# BUS_LCD.net
KiCad netlist of a schematic drawn in Altium Designer
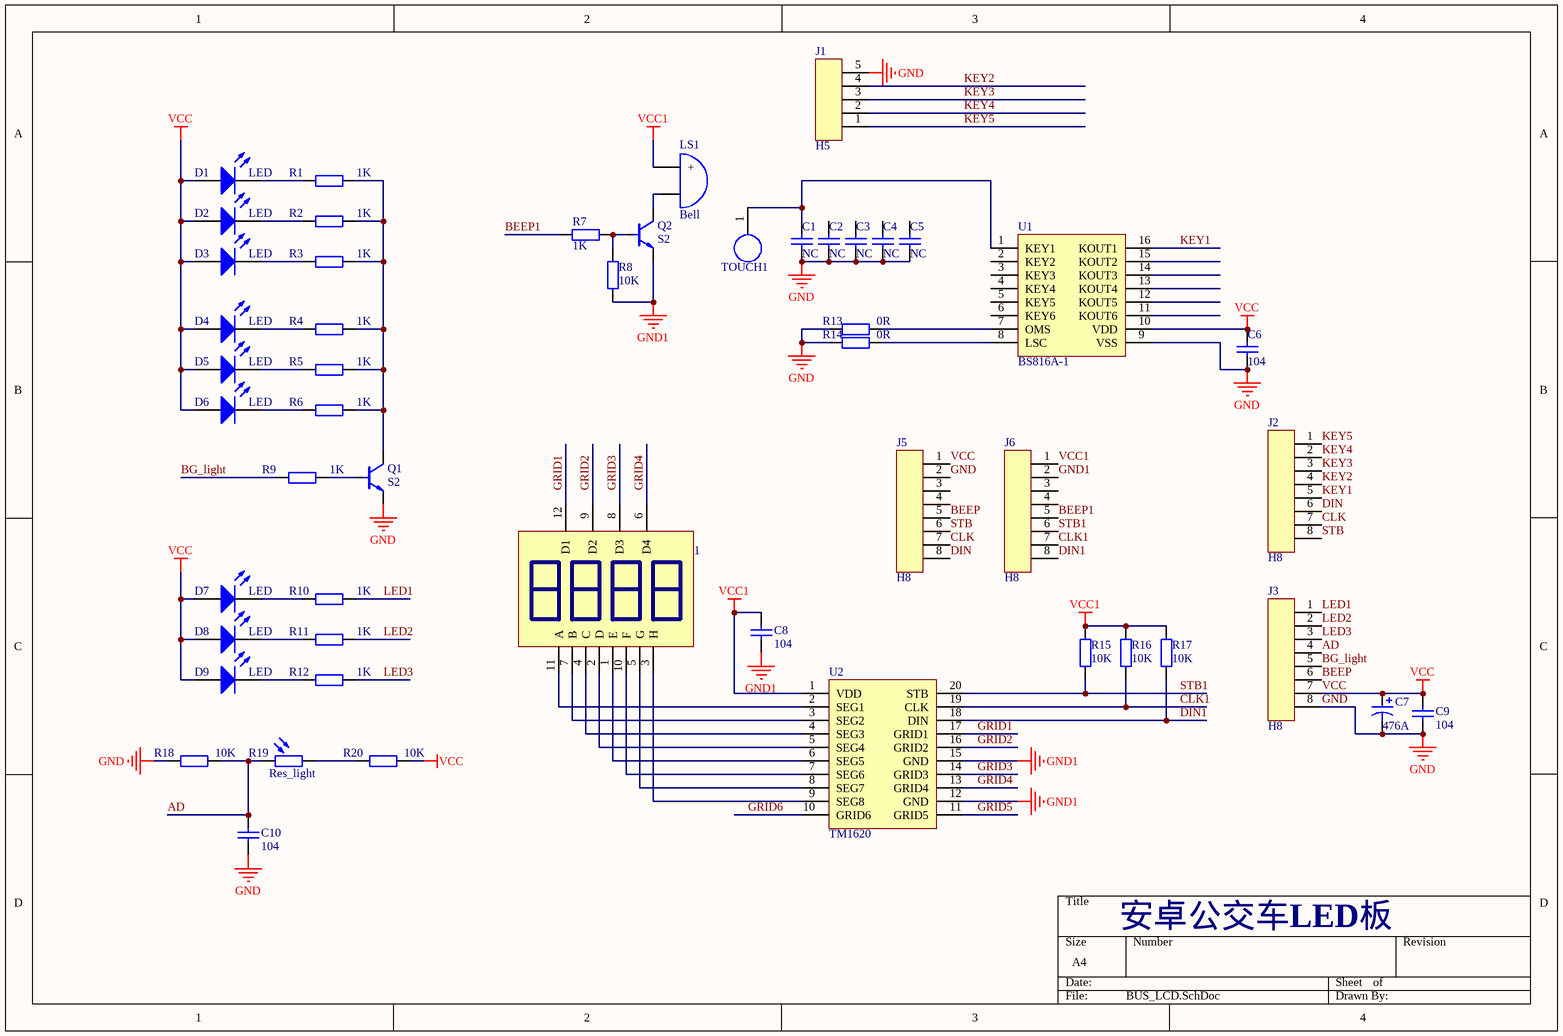
[diagram p0: BUS_LCD.SchDoc]

(export (version "E")
  (design (tool "Eeschema 10.0.6"))
  (components
    (comp (ref "1")
      (value "7SEG-MPX4")
      (footprint "7SEG-MPX4-0.36")
      (libsource (lib "QB-Special-Schlib") (part "7SEG-MPX4"))
    )
    (comp (ref "C1")
      (value "NC")
      (footprint "C0603")
      (description "Capacitor")
      (fields (field (name "PUBLISHER") "Altium Limited"))
      (libsource (lib "QB-General-Schlib") (part "Cap"))
    )
    (comp (ref "C2")
      (value "NC")
      (footprint "C0603")
      (description "Capacitor")
      (fields (field (name "PUBLISHER") "Altium Limited"))
      (libsource (lib "QB-General-Schlib") (part "Cap"))
    )
    (comp (ref "C3")
      (value "NC")
      (footprint "C0603")
      (description "Capacitor")
      (fields (field (name "PUBLISHER") "Altium Limited"))
      (libsource (lib "QB-General-Schlib") (part "Cap"))
    )
    (comp (ref "C4")
      (value "NC")
      (footprint "C0603")
      (description "Capacitor")
      (fields (field (name "PUBLISHER") "Altium Limited"))
      (libsource (lib "QB-General-Schlib") (part "Cap"))
    )
    (comp (ref "C5")
      (value "NC")
      (footprint "C0603")
      (description "Capacitor")
      (fields (field (name "PUBLISHER") "Altium Limited"))
      (libsource (lib "QB-General-Schlib") (part "Cap"))
    )
    (comp (ref "C6")
      (value "104")
      (footprint "C0603")
      (description "Capacitor")
      (fields (field (name "PUBLISHER") "Altium Limited"))
      (libsource (lib "QB-General-Schlib") (part "Cap"))
    )
    (comp (ref "C7")
      (value "476A")
      (footprint "476A")
      (description "Polarized Capacitor")
      (fields (field (name "PUBLISHER") "Altium Limited"))
      (libsource (lib "QB-General-Schlib") (part "Cap Pol"))
    )
    (comp (ref "C8")
      (value "104")
      (footprint "C0603")
      (description "Capacitor")
      (fields (field (name "PUBLISHER") "Altium Limited"))
      (libsource (lib "QB-General-Schlib") (part "Cap"))
    )
    (comp (ref "C9")
      (value "104")
      (footprint "C0603")
      (description "Capacitor")
      (fields (field (name "PUBLISHER") "Altium Limited"))
      (libsource (lib "QB-General-Schlib") (part "Cap"))
    )
    (comp (ref "C10")
      (value "104")
      (footprint "C0603")
      (description "Capacitor")
      (fields (field (name "PUBLISHER") "Altium Limited"))
      (libsource (lib "QB-General-Schlib") (part "Cap"))
    )
    (comp (ref "D1")
      (value "LED")
      (footprint "LED0805-SMT")
      (description "LED light")
      (libsource (lib "QB-General-Schlib") (part "LED"))
    )
    (comp (ref "D2")
      (value "LED")
      (footprint "LED0805-SMT")
      (description "LED light")
      (libsource (lib "QB-General-Schlib") (part "LED"))
    )
    (comp (ref "D3")
      (value "LED")
      (footprint "LED0805-SMT")
      (description "LED light")
      (libsource (lib "QB-General-Schlib") (part "LED"))
    )
    (comp (ref "D4")
      (value "LED")
      (footprint "LED0805-SMT")
      (description "LED light")
      (libsource (lib "QB-General-Schlib") (part "LED"))
    )
    (comp (ref "D5")
      (value "LED")
      (footprint "LED0805-SMT")
      (description "LED light")
      (libsource (lib "QB-General-Schlib") (part "LED"))
    )
    (comp (ref "D6")
      (value "LED")
      (footprint "LED0805-SMT")
      (description "LED light")
      (libsource (lib "QB-General-Schlib") (part "LED"))
    )
    (comp (ref "D7")
      (value "LED")
      (footprint "LED0805-SMT")
      (description "LED light")
      (libsource (lib "QB-General-Schlib") (part "LED"))
    )
    (comp (ref "D8")
      (value "LED")
      (footprint "LED0805-SMT")
      (description "LED light")
      (libsource (lib "QB-General-Schlib") (part "LED"))
    )
    (comp (ref "D9")
      (value "LED")
      (footprint "LED0805-SMT")
      (description "LED light")
      (libsource (lib "QB-General-Schlib") (part "LED"))
    )
    (comp (ref "J1") (value "H5") (footprint "H5_2.54") (libsource (lib "QB-Connector-Schlib") (part "H5")))
    (comp (ref "J2")
      (value "H8")
      (footprint "1.25-8P-LT")
      (libsource (lib "QB-Connector-Schlib") (part "H8"))
    )
    (comp (ref "J3")
      (value "H8")
      (footprint "1.25-8P-LT")
      (libsource (lib "QB-Connector-Schlib") (part "H8"))
    )
    (comp (ref "J5")
      (value "H8")
      (footprint "1.25-8P-LT")
      (libsource (lib "QB-Connector-Schlib") (part "H8"))
    )
    (comp (ref "J6")
      (value "H8")
      (footprint "1.25-8P-LT")
      (libsource (lib "QB-Connector-Schlib") (part "H8"))
    )
    (comp (ref "LS1")
      (value "Bell")
      (footprint "Bell_12*9")
      (description "Electrical Bell")
      (fields (field (name "PUBLISHER") "Altium Limited"))
      (libsource (lib "QB-Special-Schlib") (part "Bell"))
    )
    (comp (ref "Q1")
      (value "S2")
      (footprint "SOT-23")
      (description "NPN General Purpose Amplifier")
      (libsource (lib "QB-General-Schlib") (part "NPN"))
    )
    (comp (ref "Q2")
      (value "S2")
      (footprint "SOT-23")
      (description "NPN General Purpose Amplifier")
      (libsource (lib "QB-General-Schlib") (part "NPN"))
    )
    (comp (ref "R1")
      (value "1K")
      (footprint "R0603")
      (description "Resistor")
      (fields (field (name "PUBLISHER") "Altium Limited"))
      (libsource (lib "QB-General-Schlib") (part "Res"))
    )
    (comp (ref "R2")
      (value "1K")
      (footprint "R0603")
      (description "Resistor")
      (fields (field (name "PUBLISHER") "Altium Limited"))
      (libsource (lib "QB-General-Schlib") (part "Res"))
    )
    (comp (ref "R3")
      (value "1K")
      (footprint "R0603")
      (description "Resistor")
      (fields (field (name "PUBLISHER") "Altium Limited"))
      (libsource (lib "QB-General-Schlib") (part "Res"))
    )
    (comp (ref "R4")
      (value "1K")
      (footprint "R0603")
      (description "Resistor")
      (fields (field (name "PUBLISHER") "Altium Limited"))
      (libsource (lib "QB-General-Schlib") (part "Res"))
    )
    (comp (ref "R5")
      (value "1K")
      (footprint "R0603")
      (description "Resistor")
      (fields (field (name "PUBLISHER") "Altium Limited"))
      (libsource (lib "QB-General-Schlib") (part "Res"))
    )
    (comp (ref "R6")
      (value "1K")
      (footprint "R0603")
      (description "Resistor")
      (fields (field (name "PUBLISHER") "Altium Limited"))
      (libsource (lib "QB-General-Schlib") (part "Res"))
    )
    (comp (ref "R7")
      (value "1K")
      (footprint "0603R")
      (description "Resistor")
      (fields (field (name "PUBLISHER") "Altium Limited"))
      (libsource (lib "QB-General-Schlib") (part "Res"))
    )
    (comp (ref "R8")
      (value "10K")
      (footprint "0603R")
      (description "Resistor")
      (fields (field (name "PUBLISHER") "Altium Limited"))
      (libsource (lib "") (part "Res_2"))
    )
    (comp (ref "R9")
      (value "1K")
      (footprint "R0603")
      (description "Resistor")
      (fields (field (name "PUBLISHER") "Altium Limited"))
      (libsource (lib "QB-General-Schlib") (part "Res"))
    )
    (comp (ref "R10")
      (value "1K")
      (footprint "R0603")
      (description "Resistor")
      (fields (field (name "PUBLISHER") "Altium Limited"))
      (libsource (lib "QB-General-Schlib") (part "Res"))
    )
    (comp (ref "R11")
      (value "1K")
      (footprint "R0603")
      (description "Resistor")
      (fields (field (name "PUBLISHER") "Altium Limited"))
      (libsource (lib "QB-General-Schlib") (part "Res"))
    )
    (comp (ref "R12")
      (value "1K")
      (footprint "R0603")
      (description "Resistor")
      (fields (field (name "PUBLISHER") "Altium Limited"))
      (libsource (lib "QB-General-Schlib") (part "Res"))
    )
    (comp (ref "R13")
      (value "0R")
      (footprint "R0603")
      (description "Resistor")
      (fields (field (name "PUBLISHER") "Altium Limited"))
      (libsource (lib "") (part "Res_1"))
    )
    (comp (ref "R14")
      (value "0R")
      (footprint "R0603")
      (description "Resistor")
      (fields (field (name "PUBLISHER") "Altium Limited"))
      (libsource (lib "") (part "Res_1"))
    )
    (comp (ref "R15")
      (value "10K")
      (footprint "R0603")
      (description "Resistor")
      (fields (field (name "PUBLISHER") "Altium Limited"))
      (libsource (lib "") (part "Res_2"))
    )
    (comp (ref "R16")
      (value "10K")
      (footprint "R0603")
      (description "Resistor")
      (fields (field (name "PUBLISHER") "Altium Limited"))
      (libsource (lib "") (part "Res_2"))
    )
    (comp (ref "R17")
      (value "10K")
      (footprint "R0603")
      (description "Resistor")
      (fields (field (name "PUBLISHER") "Altium Limited"))
      (libsource (lib "") (part "Res_2"))
    )
    (comp (ref "R18")
      (value "10K")
      (footprint "R0603")
      (description "Resistor")
      (fields (field (name "PUBLISHER") "Altium Limited"))
      (libsource (lib "QB-General-Schlib") (part "Res"))
    )
    (comp (ref "R19")
      (value "Res_light")
      (footprint "LED0805-SMT")
      (description "Light Dependent Rsistors")
      (fields (field (name "PUBLISHER") "Altium Limited"))
      (libsource (lib "QB-General-Schlib") (part "Res_light"))
    )
    (comp (ref "R20")
      (value "10K")
      (footprint "R0603")
      (description "Resistor")
      (fields (field (name "PUBLISHER") "Altium Limited"))
      (libsource (lib "QB-General-Schlib") (part "Res"))
    )
    (comp (ref "TOUCH1")
      (value "TouchKey1")
      (footprint "TOUCHKEY6")
      (libsource (lib "QB-Special-Schlib") (part "TouchKey1"))
    )
    (comp (ref "U1")
      (value "BS816A-1")
      (footprint "SO-16")
      (libsource (lib "QB-Chip-Schlib") (part "BS816A-1"))
    )
    (comp (ref "U2")
      (value "TM1620")
      (footprint "SOJ-20")
      (description "数码管驱动")
      (libsource (lib "QB-Chip-Schlib") (part "TM1620"))
    )
  )
  (nets
    (net (code "1") (name "/AD") (class "Default")
      (node (ref "C10") (pin "2") (pinfunction "2_2") (pintype "passive"))
      (node (ref "J3") (pin "4") (pinfunction "4_4") (pintype "passive"))
      (node (ref "R18") (pin "2") (pinfunction "2_2") (pintype "passive"))
      (node (ref "R19") (pin "2") (pinfunction "2_2") (pintype "passive"))
    )
    (net (code "2") (name "/BEEP") (class "Default")
      (node (ref "J3") (pin "6") (pinfunction "6_6") (pintype "passive"))
      (node (ref "J5") (pin "5") (pinfunction "5_5") (pintype "passive"))
    )
    (net (code "3") (name "/BEEP1") (class "Default")
      (node (ref "J6") (pin "5") (pinfunction "5_5") (pintype "passive"))
      (node (ref "R7") (pin "1") (pinfunction "1_1") (pintype "passive"))
    )
    (net (code "4") (name "/BG_light") (class "Default")
      (node (ref "J3") (pin "5") (pinfunction "5_5") (pintype "passive"))
      (node (ref "R9") (pin "1") (pinfunction "1_1") (pintype "passive"))
    )
    (net (code "5") (name "/CLK") (class "Default")
      (node (ref "J2") (pin "7") (pinfunction "7_7") (pintype "passive"))
      (node (ref "J5") (pin "7") (pinfunction "7_7") (pintype "passive"))
    )
    (net (code "6") (name "/CLK1") (class "Default")
      (node (ref "J6") (pin "7") (pinfunction "7_7") (pintype "passive"))
      (node (ref "R16") (pin "1") (pinfunction "1_1") (pintype "passive"))
      (node (ref "U2") (pin "19") (pinfunction "CLK_19") (pintype "passive"))
    )
    (net (code "7") (name "/DIN") (class "Default")
      (node (ref "J2") (pin "6") (pinfunction "6_6") (pintype "passive"))
      (node (ref "J5") (pin "8") (pinfunction "8_8") (pintype "passive"))
    )
    (net (code "8") (name "/DIN1") (class "Default")
      (node (ref "J6") (pin "8") (pinfunction "8_8") (pintype "passive"))
      (node (ref "R17") (pin "1") (pinfunction "1_1") (pintype "passive"))
      (node (ref "U2") (pin "18") (pinfunction "DIN_18") (pintype "passive"))
    )
    (net (code "9") (name "/GRID1") (class "Default")
      (node (ref "1") (pin "12") (pinfunction "D1_12") (pintype "passive"))
      (node (ref "U2") (pin "17") (pinfunction "GRID1_17") (pintype "passive"))
    )
    (net (code "10") (name "/GRID2") (class "Default")
      (node (ref "1") (pin "9") (pinfunction "D2_9") (pintype "passive"))
      (node (ref "U2") (pin "16") (pinfunction "GRID2_16") (pintype "passive"))
    )
    (net (code "11") (name "/GRID3") (class "Default")
      (node (ref "1") (pin "8") (pinfunction "D3_8") (pintype "passive"))
      (node (ref "U2") (pin "14") (pinfunction "GRID3_14") (pintype "passive"))
    )
    (net (code "12") (name "/GRID4") (class "Default")
      (node (ref "1") (pin "6") (pinfunction "D4_6") (pintype "passive"))
      (node (ref "U2") (pin "13") (pinfunction "GRID4_13") (pintype "passive"))
    )
    (net (code "13") (name "/GRID5") (class "Default")
      (node (ref "U2") (pin "11") (pinfunction "GRID5_11") (pintype "passive"))
    )
    (net (code "14") (name "/GRID6") (class "Default")
      (node (ref "U2") (pin "10") (pinfunction "GRID6_10") (pintype "passive"))
    )
    (net (code "15") (name "/KEY1") (class "Default")
      (node (ref "J2") (pin "5") (pinfunction "5_5") (pintype "passive"))
      (node (ref "U1") (pin "16") (pinfunction "KOUT1_16") (pintype "passive"))
    )
    (net (code "16") (name "/KEY2") (class "Default")
      (node (ref "J1") (pin "4") (pinfunction "4_4") (pintype "passive"))
      (node (ref "J2") (pin "4") (pinfunction "4_4") (pintype "passive"))
    )
    (net (code "17") (name "/KEY3") (class "Default")
      (node (ref "J1") (pin "3") (pinfunction "3_3") (pintype "passive"))
      (node (ref "J2") (pin "3") (pinfunction "3_3") (pintype "passive"))
    )
    (net (code "18") (name "/KEY4") (class "Default")
      (node (ref "J1") (pin "2") (pinfunction "2_2") (pintype "passive"))
      (node (ref "J2") (pin "2") (pinfunction "2_2") (pintype "passive"))
    )
    (net (code "19") (name "/KEY5") (class "Default")
      (node (ref "J1") (pin "1") (pinfunction "1_1") (pintype "passive"))
      (node (ref "J2") (pin "1") (pinfunction "1_1") (pintype "passive"))
    )
    (net (code "20") (name "/LED1") (class "Default")
      (node (ref "J3") (pin "1") (pinfunction "1_1") (pintype "passive"))
      (node (ref "R10") (pin "2") (pinfunction "2_2") (pintype "passive"))
    )
    (net (code "21") (name "/LED2") (class "Default")
      (node (ref "J3") (pin "2") (pinfunction "2_2") (pintype "passive"))
      (node (ref "R11") (pin "2") (pinfunction "2_2") (pintype "passive"))
    )
    (net (code "22") (name "/LED3") (class "Default")
      (node (ref "J3") (pin "3") (pinfunction "3_3") (pintype "passive"))
      (node (ref "R12") (pin "2") (pinfunction "2_2") (pintype "passive"))
    )
    (net (code "23") (name "/STB") (class "Default")
      (node (ref "J2") (pin "8") (pinfunction "8_8") (pintype "passive"))
      (node (ref "J5") (pin "6") (pinfunction "6_6") (pintype "passive"))
    )
    (net (code "24") (name "/STB1") (class "Default")
      (node (ref "J6") (pin "6") (pinfunction "6_6") (pintype "passive"))
      (node (ref "R15") (pin "1") (pinfunction "1_1") (pintype "passive"))
      (node (ref "U2") (pin "20") (pinfunction "STB_20") (pintype "passive"))
    )
    (net (code "25") (name "GND") (class "Default")
      (node (ref "C1") (pin "1") (pinfunction "1_1") (pintype "passive"))
      (node (ref "C10") (pin "1") (pinfunction "1_1") (pintype "passive"))
      (node (ref "C2") (pin "1") (pinfunction "1_1") (pintype "passive"))
      (node (ref "C3") (pin "1") (pinfunction "1_1") (pintype "passive"))
      (node (ref "C4") (pin "1") (pinfunction "1_1") (pintype "passive"))
      (node (ref "C5") (pin "1") (pinfunction "1_1") (pintype "passive"))
      (node (ref "C6") (pin "1") (pinfunction "1_1") (pintype "passive"))
      (node (ref "C7") (pin "2") (pinfunction "2_2") (pintype "passive"))
      (node (ref "C9") (pin "1") (pinfunction "1_1") (pintype "passive"))
      (node (ref "J1") (pin "5") (pinfunction "5_5") (pintype "passive"))
      (node (ref "J3") (pin "8") (pinfunction "8_8") (pintype "passive"))
      (node (ref "J5") (pin "2") (pinfunction "2_2") (pintype "passive"))
      (node (ref "Q1") (pin "1") (pinfunction "e_1") (pintype "passive"))
      (node (ref "R13") (pin "2") (pinfunction "2_2") (pintype "passive"))
      (node (ref "R14") (pin "2") (pinfunction "2_2") (pintype "passive"))
      (node (ref "R18") (pin "1") (pinfunction "1_1") (pintype "passive"))
      (node (ref "U1") (pin "9") (pinfunction "VSS_9") (pintype "passive"))
    )
    (net (code "26") (name "GND1") (class "Default")
      (node (ref "C8") (pin "1") (pinfunction "1_1") (pintype "passive"))
      (node (ref "J6") (pin "2") (pinfunction "2_2") (pintype "passive"))
      (node (ref "Q2") (pin "1") (pinfunction "e_1") (pintype "passive"))
      (node (ref "R8") (pin "1") (pinfunction "1_1") (pintype "passive"))
      (node (ref "U2") (pin "12") (pinfunction "GND_12") (pintype "passive"))
      (node (ref "U2") (pin "15") (pinfunction "GND_15") (pintype "passive"))
    )
    (net (code "27") (name "Net-(1-A)") (class "Default")
      (node (ref "1") (pin "11") (pinfunction "A_11") (pintype "passive"))
      (node (ref "U2") (pin "2") (pinfunction "SEG1_2") (pintype "passive"))
    )
    (net (code "28") (name "Net-(1-B)") (class "Default")
      (node (ref "1") (pin "7") (pinfunction "B_7") (pintype "passive"))
      (node (ref "U2") (pin "3") (pinfunction "SEG2_3") (pintype "passive"))
    )
    (net (code "29") (name "Net-(1-C)") (class "Default")
      (node (ref "1") (pin "4") (pinfunction "C_4") (pintype "passive"))
      (node (ref "U2") (pin "4") (pinfunction "SEG3_4") (pintype "passive"))
    )
    (net (code "30") (name "Net-(1-D)") (class "Default")
      (node (ref "1") (pin "2") (pinfunction "D_2") (pintype "passive"))
      (node (ref "U2") (pin "5") (pinfunction "SEG4_5") (pintype "passive"))
    )
    (net (code "31") (name "Net-(1-E)") (class "Default")
      (node (ref "1") (pin "1") (pinfunction "E_1") (pintype "passive"))
      (node (ref "U2") (pin "6") (pinfunction "SEG5_6") (pintype "passive"))
    )
    (net (code "32") (name "Net-(1-F)") (class "Default")
      (node (ref "1") (pin "10") (pinfunction "F_10") (pintype "passive"))
      (node (ref "U2") (pin "7") (pinfunction "SEG6_7") (pintype "passive"))
    )
    (net (code "33") (name "Net-(1-G)") (class "Default")
      (node (ref "1") (pin "5") (pinfunction "G_5") (pintype "passive"))
      (node (ref "U2") (pin "8") (pinfunction "SEG7_8") (pintype "passive"))
    )
    (net (code "34") (name "Net-(1-H)") (class "Default")
      (node (ref "1") (pin "3") (pinfunction "H_3") (pintype "passive"))
      (node (ref "U2") (pin "9") (pinfunction "SEG8_9") (pintype "passive"))
    )
    (net (code "35") (name "Net-(D1-K)") (class "Default")
      (node (ref "D1") (pin "2") (pinfunction "K_2") (pintype "passive"))
      (node (ref "R1") (pin "1") (pinfunction "1_1") (pintype "passive"))
    )
    (net (code "36") (name "Net-(D2-K)") (class "Default")
      (node (ref "D2") (pin "2") (pinfunction "K_2") (pintype "passive"))
      (node (ref "R2") (pin "1") (pinfunction "1_1") (pintype "passive"))
    )
    (net (code "37") (name "Net-(D3-K)") (class "Default")
      (node (ref "D3") (pin "2") (pinfunction "K_2") (pintype "passive"))
      (node (ref "R3") (pin "1") (pinfunction "1_1") (pintype "passive"))
    )
    (net (code "38") (name "Net-(D4-K)") (class "Default")
      (node (ref "D4") (pin "2") (pinfunction "K_2") (pintype "passive"))
      (node (ref "R4") (pin "1") (pinfunction "1_1") (pintype "passive"))
    )
    (net (code "39") (name "Net-(D5-K)") (class "Default")
      (node (ref "D5") (pin "2") (pinfunction "K_2") (pintype "passive"))
      (node (ref "R5") (pin "1") (pinfunction "1_1") (pintype "passive"))
    )
    (net (code "40") (name "Net-(D6-K)") (class "Default")
      (node (ref "D6") (pin "2") (pinfunction "K_2") (pintype "passive"))
      (node (ref "R6") (pin "1") (pinfunction "1_1") (pintype "passive"))
    )
    (net (code "41") (name "Net-(D7-K)") (class "Default")
      (node (ref "D7") (pin "2") (pinfunction "K_2") (pintype "passive"))
      (node (ref "R10") (pin "1") (pinfunction "1_1") (pintype "passive"))
    )
    (net (code "42") (name "Net-(D8-K)") (class "Default")
      (node (ref "D8") (pin "2") (pinfunction "K_2") (pintype "passive"))
      (node (ref "R11") (pin "1") (pinfunction "1_1") (pintype "passive"))
    )
    (net (code "43") (name "Net-(D9-K)") (class "Default")
      (node (ref "D9") (pin "2") (pinfunction "K_2") (pintype "passive"))
      (node (ref "R12") (pin "1") (pinfunction "1_1") (pintype "passive"))
    )
    (net (code "44") (name "Net-(LS1--)") (class "Default")
      (node (ref "LS1") (pin "2") (pinfunction "-_2") (pintype "passive"))
      (node (ref "Q2") (pin "3") (pinfunction "c_3") (pintype "passive"))
    )
    (net (code "45") (name "Net-(Q1-b)") (class "Default")
      (node (ref "Q1") (pin "2") (pinfunction "b_2") (pintype "passive"))
      (node (ref "R9") (pin "2") (pinfunction "2_2") (pintype "passive"))
    )
    (net (code "46") (name "Net-(Q1-c)") (class "Default")
      (node (ref "Q1") (pin "3") (pinfunction "c_3") (pintype "passive"))
      (node (ref "R1") (pin "2") (pinfunction "2_2") (pintype "passive"))
      (node (ref "R2") (pin "2") (pinfunction "2_2") (pintype "passive"))
      (node (ref "R3") (pin "2") (pinfunction "2_2") (pintype "passive"))
      (node (ref "R4") (pin "2") (pinfunction "2_2") (pintype "passive"))
      (node (ref "R5") (pin "2") (pinfunction "2_2") (pintype "passive"))
      (node (ref "R6") (pin "2") (pinfunction "2_2") (pintype "passive"))
    )
    (net (code "47") (name "Net-(Q2-b)") (class "Default")
      (node (ref "Q2") (pin "2") (pinfunction "b_2") (pintype "passive"))
      (node (ref "R7") (pin "2") (pinfunction "2_2") (pintype "passive"))
      (node (ref "R8") (pin "2") (pinfunction "2_2") (pintype "passive"))
    )
    (net (code "48") (name "Net-(R19-Pad1)") (class "Default")
      (node (ref "R19") (pin "1") (pinfunction "1_1") (pintype "passive"))
      (node (ref "R20") (pin "1") (pinfunction "1_1") (pintype "passive"))
    )
    (net (code "49") (name "Net-(U1-KEY1)") (class "Default")
      (node (ref "C1") (pin "2") (pinfunction "2_2") (pintype "passive"))
      (node (ref "TOUCH1") (pin "1") (pinfunction "1_1") (pintype "passive"))
      (node (ref "U1") (pin "1") (pinfunction "KEY1_1") (pintype "passive"))
    )
    (net (code "50") (name "Net-(U1-LSC)") (class "Default")
      (node (ref "R14") (pin "1") (pinfunction "1_1") (pintype "passive"))
      (node (ref "U1") (pin "8") (pinfunction "LSC_8") (pintype "passive"))
    )
    (net (code "51") (name "Net-(U1-OMS)") (class "Default")
      (node (ref "R13") (pin "1") (pinfunction "1_1") (pintype "passive"))
      (node (ref "U1") (pin "7") (pinfunction "OMS_7") (pintype "passive"))
    )
    (net (code "52") (name "VCC") (class "Default")
      (node (ref "C6") (pin "2") (pinfunction "2_2") (pintype "passive"))
      (node (ref "C7") (pin "1") (pinfunction "1_1") (pintype "passive"))
      (node (ref "C9") (pin "2") (pinfunction "2_2") (pintype "passive"))
      (node (ref "D1") (pin "1") (pinfunction "A_1") (pintype "passive"))
      (node (ref "D2") (pin "1") (pinfunction "A_1") (pintype "passive"))
      (node (ref "D3") (pin "1") (pinfunction "A_1") (pintype "passive"))
      (node (ref "D4") (pin "1") (pinfunction "A_1") (pintype "passive"))
      (node (ref "D5") (pin "1") (pinfunction "A_1") (pintype "passive"))
      (node (ref "D6") (pin "1") (pinfunction "A_1") (pintype "passive"))
      (node (ref "D7") (pin "1") (pinfunction "A_1") (pintype "passive"))
      (node (ref "D8") (pin "1") (pinfunction "A_1") (pintype "passive"))
      (node (ref "D9") (pin "1") (pinfunction "A_1") (pintype "passive"))
      (node (ref "J3") (pin "7") (pinfunction "7_7") (pintype "passive"))
      (node (ref "J5") (pin "1") (pinfunction "1_1") (pintype "passive"))
      (node (ref "R20") (pin "2") (pinfunction "2_2") (pintype "passive"))
      (node (ref "U1") (pin "10") (pinfunction "VDD_10") (pintype "passive"))
    )
    (net (code "53") (name "VCC1") (class "Default")
      (node (ref "C8") (pin "2") (pinfunction "2_2") (pintype "passive"))
      (node (ref "J6") (pin "1") (pinfunction "1_1") (pintype "passive"))
      (node (ref "LS1") (pin "1") (pinfunction "+_1") (pintype "passive"))
      (node (ref "R15") (pin "2") (pinfunction "2_2") (pintype "passive"))
      (node (ref "R16") (pin "2") (pinfunction "2_2") (pintype "passive"))
      (node (ref "R17") (pin "2") (pinfunction "2_2") (pintype "passive"))
      (node (ref "U2") (pin "1") (pinfunction "VDD_1") (pintype "passive"))
    )
    (net (code "54") (name "unconnected-(C2-Pad2)") (class "Default")
      (node (ref "C2") (pin "2") (pinfunction "2_2") (pintype "passive"))
    )
    (net (code "55") (name "unconnected-(C3-Pad2)") (class "Default")
      (node (ref "C3") (pin "2") (pinfunction "2_2") (pintype "passive"))
    )
    (net (code "56") (name "unconnected-(C4-Pad2)") (class "Default")
      (node (ref "C4") (pin "2") (pinfunction "2_2") (pintype "passive"))
    )
    (net (code "57") (name "unconnected-(C5-Pad2)") (class "Default")
      (node (ref "C5") (pin "2") (pinfunction "2_2") (pintype "passive"))
    )
    (net (code "58") (name "unconnected-(J5-Pad3)") (class "Default")
      (node (ref "J5") (pin "3") (pinfunction "3_3") (pintype "passive"))
    )
    (net (code "59") (name "unconnected-(J5-Pad4)") (class "Default")
      (node (ref "J5") (pin "4") (pinfunction "4_4") (pintype "passive"))
    )
    (net (code "60") (name "unconnected-(J6-Pad3)") (class "Default")
      (node (ref "J6") (pin "3") (pinfunction "3_3") (pintype "passive"))
    )
    (net (code "61") (name "unconnected-(J6-Pad4)") (class "Default")
      (node (ref "J6") (pin "4") (pinfunction "4_4") (pintype "passive"))
    )
    (net (code "62") (name "unconnected-(U1-KEY2-Pad2)") (class "Default")
      (node (ref "U1") (pin "2") (pinfunction "KEY2_2") (pintype "passive"))
    )
    (net (code "63") (name "unconnected-(U1-KEY3-Pad3)") (class "Default")
      (node (ref "U1") (pin "3") (pinfunction "KEY3_3") (pintype "passive"))
    )
    (net (code "64") (name "unconnected-(U1-KEY4-Pad4)") (class "Default")
      (node (ref "U1") (pin "4") (pinfunction "KEY4_4") (pintype "passive"))
    )
    (net (code "65") (name "unconnected-(U1-KEY5-Pad5)") (class "Default")
      (node (ref "U1") (pin "5") (pinfunction "KEY5_5") (pintype "passive"))
    )
    (net (code "66") (name "unconnected-(U1-KEY6-Pad6)") (class "Default")
      (node (ref "U1") (pin "6") (pinfunction "KEY6_6") (pintype "passive"))
    )
    (net (code "67") (name "unconnected-(U1-KOUT2-Pad15)") (class "Default")
      (node (ref "U1") (pin "15") (pinfunction "KOUT2_15") (pintype "passive"))
    )
    (net (code "68") (name "unconnected-(U1-KOUT3-Pad14)") (class "Default")
      (node (ref "U1") (pin "14") (pinfunction "KOUT3_14") (pintype "passive"))
    )
    (net (code "69") (name "unconnected-(U1-KOUT4-Pad13)") (class "Default")
      (node (ref "U1") (pin "13") (pinfunction "KOUT4_13") (pintype "passive"))
    )
    (net (code "70") (name "unconnected-(U1-KOUT5-Pad12)") (class "Default")
      (node (ref "U1") (pin "12") (pinfunction "KOUT5_12") (pintype "passive"))
    )
    (net (code "71") (name "unconnected-(U1-KOUT6-Pad11)") (class "Default")
      (node (ref "U1") (pin "11") (pinfunction "KOUT6_11") (pintype "passive"))
    )
  )
)
